# bcd_to_7segment.net
KiCad netlist of a schematic drawn in EAGLE
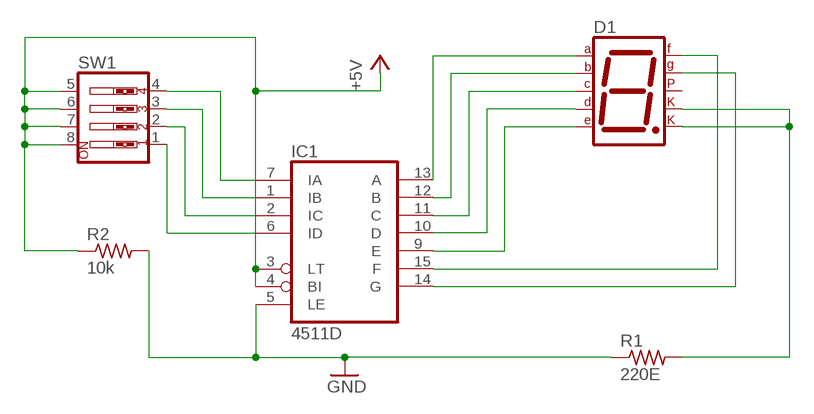
[diagram p0: schematic, sheet 1]

(export (version "E")
  (design (tool "Eeschema 10.0.6"))
  (components
    (comp (ref "D1")
      (value "7SEG-CK")
      (footprint "eagle-import:7SEG-13")
      (libsource (lib "eagle-import") (part "7SEG-CK"))
    )
    (comp (ref "IC1")
      (value "4511D")
      (footprint "eagle-import:SO16")
      (libsource (lib "eagle-import") (part "4511D"))
    )
    (comp (ref "R1")
      (value "220E")
      (footprint "eagle-import:R0603")
      (libsource (lib "eagle-import") (part "R-US_R0603"))
    )
    (comp (ref "R2")
      (value "10k")
      (footprint "eagle-import:R0603")
      (libsource (lib "eagle-import") (part "R-US_R0603"))
    )
    (comp (ref "SW1")
      (value "SW_DIP-4")
      (footprint "eagle-import:EDG-04")
      (libsource (lib "eagle-import") (part "SW_DIP-4"))
    )
  )
  (nets
    (net (code "1") (name "+5V") (class "Default")
      (node (ref "IC1") (pin "3") (pinfunction "LT_3") (pintype "input"))
      (node (ref "IC1") (pin "4") (pinfunction "BI_4") (pintype "input"))
      (node (ref "R2") (pin "1") (pinfunction "1_1") (pintype "passive"))
      (node (ref "SW1") (pin "5") (pinfunction "5_5") (pintype "passive"))
      (node (ref "SW1") (pin "6") (pinfunction "6_6") (pintype "passive"))
      (node (ref "SW1") (pin "7") (pinfunction "7_7") (pintype "passive"))
      (node (ref "SW1") (pin "8") (pinfunction "8_8") (pintype "passive"))
    )
    (net (code "2") (name "GND") (class "Default")
      (node (ref "IC1") (pin "5") (pinfunction "LE_5") (pintype "input"))
      (node (ref "R1") (pin "1") (pinfunction "1_1") (pintype "passive"))
      (node (ref "R2") (pin "2") (pinfunction "2_2") (pintype "passive"))
    )
    (net (code "3") (name "Net-(D1-A)") (class "Default")
      (node (ref "D1") (pin "7") (pinfunction "A_7") (pintype "passive"))
      (node (ref "IC1") (pin "13") (pinfunction "A_13") (pintype "output"))
    )
    (net (code "4") (name "Net-(D1-B)") (class "Default")
      (node (ref "D1") (pin "6") (pinfunction "B_6") (pintype "passive"))
      (node (ref "IC1") (pin "12") (pinfunction "B_12") (pintype "output"))
    )
    (net (code "5") (name "Net-(D1-C)") (class "Default")
      (node (ref "D1") (pin "4") (pinfunction "C_4") (pintype "passive"))
      (node (ref "IC1") (pin "11") (pinfunction "C_11") (pintype "output"))
    )
    (net (code "6") (name "Net-(D1-CK1)") (class "Default")
      (node (ref "D1") (pin "3") (pinfunction "CK1_3") (pintype "passive"))
      (node (ref "D1") (pin "8") (pinfunction "CK2_8") (pintype "passive"))
      (node (ref "R1") (pin "2") (pinfunction "2_2") (pintype "passive"))
    )
    (net (code "7") (name "Net-(D1-D)") (class "Default")
      (node (ref "D1") (pin "2") (pinfunction "D_2") (pintype "passive"))
      (node (ref "IC1") (pin "10") (pinfunction "D_10") (pintype "output"))
    )
    (net (code "8") (name "Net-(D1-E)") (class "Default")
      (node (ref "D1") (pin "1") (pinfunction "E_1") (pintype "passive"))
      (node (ref "IC1") (pin "9") (pinfunction "E_9") (pintype "output"))
    )
    (net (code "9") (name "Net-(D1-F)") (class "Default")
      (node (ref "D1") (pin "9") (pinfunction "F_9") (pintype "passive"))
      (node (ref "IC1") (pin "15") (pinfunction "F_15") (pintype "output"))
    )
    (net (code "10") (name "Net-(D1-G)") (class "Default")
      (node (ref "D1") (pin "10") (pinfunction "G_10") (pintype "passive"))
      (node (ref "IC1") (pin "14") (pinfunction "G_14") (pintype "output"))
    )
    (net (code "11") (name "Net-(IC1A-IA)") (class "Default")
      (node (ref "IC1") (pin "7") (pinfunction "IA_7") (pintype "input"))
      (node (ref "SW1") (pin "4") (pinfunction "4_4") (pintype "passive"))
    )
    (net (code "12") (name "Net-(IC1A-IB)") (class "Default")
      (node (ref "IC1") (pin "1") (pinfunction "IB_1") (pintype "input"))
      (node (ref "SW1") (pin "3") (pinfunction "3_3") (pintype "passive"))
    )
    (net (code "13") (name "Net-(IC1A-IC)") (class "Default")
      (node (ref "IC1") (pin "2") (pinfunction "IC_2") (pintype "input"))
      (node (ref "SW1") (pin "2") (pinfunction "2_2") (pintype "passive"))
    )
    (net (code "14") (name "Net-(IC1A-ID)") (class "Default")
      (node (ref "IC1") (pin "6") (pinfunction "ID_6") (pintype "input"))
      (node (ref "SW1") (pin "1") (pinfunction "1_1") (pintype "passive"))
    )
    (net (code "15") (name "unconnected-(D1-DP-Pad5)") (class "Default")
      (node (ref "D1") (pin "5") (pinfunction "DP_5") (pintype "passive"))
    )
  )
)
